# SFXboard.net
KiCad netlist of a schematic drawn in EAGLE
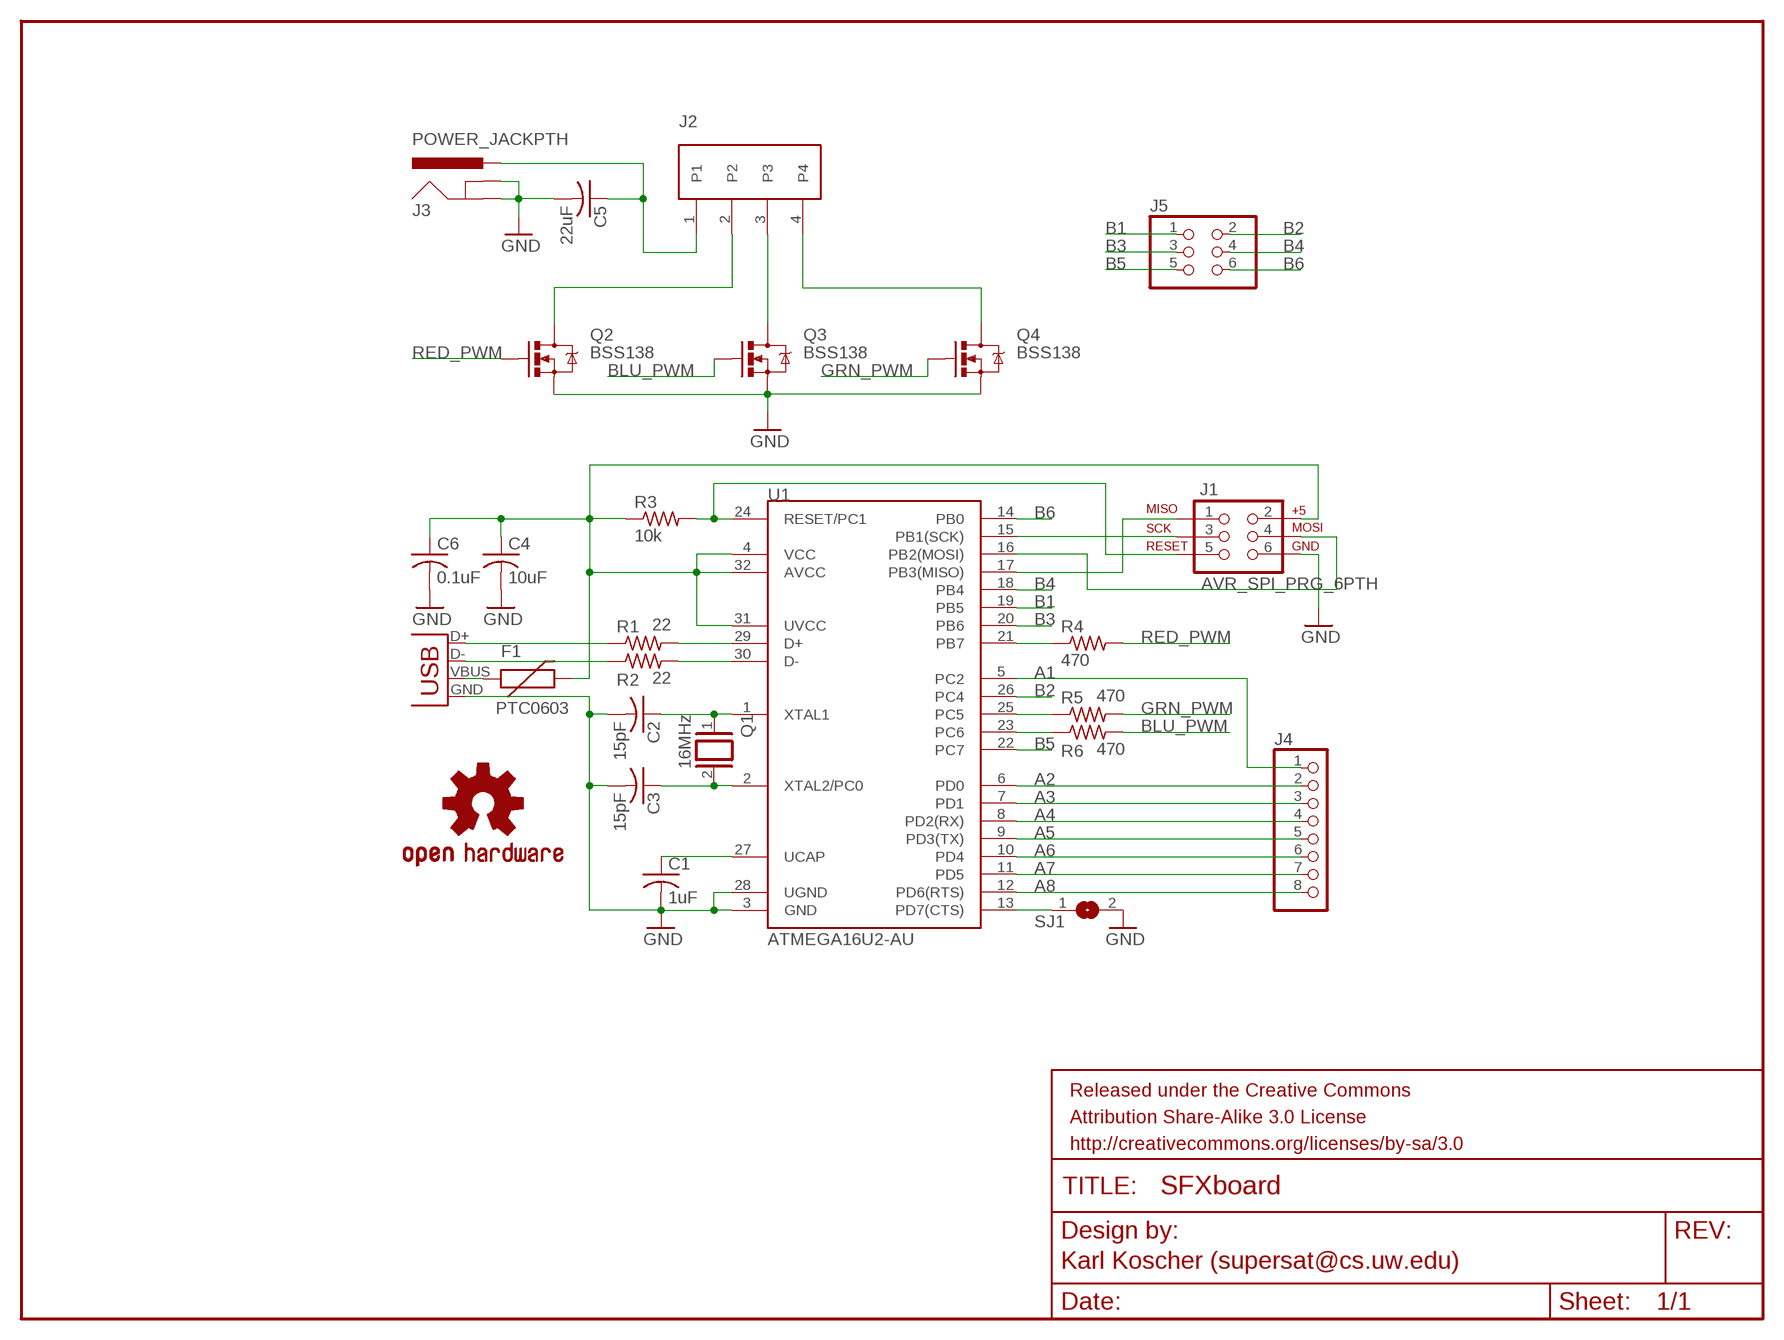
[diagram p0: schematic, sheet 1]

(export (version "E")
  (design (tool "Eeschema 10.0.6"))
  (components
    (comp (ref "C1")
      (value "1uF")
      (footprint "eagle-import:C0603")
      (libsource (lib "eagle-import") (part "C-USC0603"))
    )
    (comp (ref "C2")
      (value "15pF")
      (footprint "eagle-import:C0603")
      (libsource (lib "eagle-import") (part "C-USC0603"))
    )
    (comp (ref "C3")
      (value "15pF")
      (footprint "eagle-import:C0603")
      (libsource (lib "eagle-import") (part "C-USC0603"))
    )
    (comp (ref "C4")
      (value "10uF")
      (footprint "eagle-import:C0805")
      (libsource (lib "eagle-import") (part "C-USC0805"))
    )
    (comp (ref "C5")
      (value "22uF")
      (footprint "eagle-import:C0805")
      (libsource (lib "eagle-import") (part "C-USC0805"))
    )
    (comp (ref "C6")
      (value "0.1uF")
      (footprint "eagle-import:C0402")
      (libsource (lib "eagle-import") (part "C-USC0402"))
    )
    (comp (ref "F1")
      (value "PTC0603")
      (footprint "eagle-import:0603")
      (libsource (lib "eagle-import") (part "PTC0603"))
    )
    (comp (ref "FRAME1")
      (value "FRAME-LETTER")
      (footprint "eagle-import:CREATIVE_COMMONS")
      (libsource (lib "eagle-import") (part "FRAME-LETTER"))
    )
    (comp (ref "J1")
      (value "AVR_SPI_PRG_6PTH")
      (footprint "eagle-import:2X3")
      (libsource (lib "eagle-import") (part "AVR_SPI_PRG_6PTH"))
    )
    (comp (ref "J2")
      (value "TERMBLOCK4POS")
      (footprint "eagle-import:TERMBLOCK4P")
      (libsource (lib "eagle-import") (part "TERMBLOCK4POS"))
    )
    (comp (ref "J3")
      (value "POWER_JACKPTH")
      (footprint "eagle-import:POWER_JACK_PTH")
      (libsource (lib "eagle-import") (part "POWER_JACKPTH"))
    )
    (comp (ref "J4")
      (value "PINHD-1X8")
      (footprint "eagle-import:1X08")
      (libsource (lib "eagle-import") (part "PINHD-1X8"))
    )
    (comp (ref "J5")
      (value "PINHD-2X3")
      (footprint "eagle-import:2X03")
      (libsource (lib "eagle-import") (part "PINHD-2X3"))
    )
    (comp (ref "Q1")
      (value "16MHz")
      (footprint "eagle-import:QS")
      (libsource (lib "eagle-import") (part "XTAL/S"))
    )
    (comp (ref "Q2")
      (value "BSS138")
      (footprint "eagle-import:SOT23-3")
      (libsource (lib "eagle-import") (part "BSS138TRANS-00830"))
    )
    (comp (ref "Q3")
      (value "BSS138")
      (footprint "eagle-import:SOT23-3")
      (libsource (lib "eagle-import") (part "BSS138TRANS-00830"))
    )
    (comp (ref "Q4")
      (value "BSS138")
      (footprint "eagle-import:SOT23-3")
      (libsource (lib "eagle-import") (part "BSS138TRANS-00830"))
    )
    (comp (ref "R1")
      (value "22")
      (footprint "eagle-import:R0603")
      (libsource (lib "eagle-import") (part "R-US_R0603"))
    )
    (comp (ref "R2")
      (value "22")
      (footprint "eagle-import:R0603")
      (libsource (lib "eagle-import") (part "R-US_R0603"))
    )
    (comp (ref "R3")
      (value "10k")
      (footprint "eagle-import:R0603")
      (libsource (lib "eagle-import") (part "R-US_R0603"))
    )
    (comp (ref "R4")
      (value "470")
      (footprint "eagle-import:R0603")
      (libsource (lib "eagle-import") (part "R-US_R0603"))
    )
    (comp (ref "R5")
      (value "470")
      (footprint "eagle-import:R0603")
      (libsource (lib "eagle-import") (part "R-US_R0603"))
    )
    (comp (ref "R6")
      (value "470")
      (footprint "eagle-import:R0603")
      (libsource (lib "eagle-import") (part "R-US_R0603"))
    )
    (comp (ref "SJ1") (value "SJ") (footprint "eagle-import:SJ") (libsource (lib "eagle-import") (part "SJ")))
    (comp (ref "U$2")
      (value "OSHW-LOGOS")
      (footprint "eagle-import:OSHW-LOGO-S")
      (libsource (lib "eagle-import") (part "OSHW-LOGOS"))
    )
    (comp (ref "U1")
      (value "ATMEGA16U2-AU")
      (footprint "eagle-import:TQFP32-08")
      (libsource (lib "eagle-import") (part "ATMEGA8U2AU"))
    )
    (comp (ref "X1")
      (value "USBSMD")
      (footprint "eagle-import:USB-MINIB")
      (libsource (lib "eagle-import") (part "USBSMD"))
    )
  )
  (nets
    (net (code "1") (name "/A1") (class "Default")
      (node (ref "J4") (pin "1") (pinfunction "1_1") (pintype "passive"))
      (node (ref "U1") (pin "5") (pinfunction "PC2_5") (pintype "bidirectional"))
    )
    (net (code "2") (name "/A2") (class "Default")
      (node (ref "J4") (pin "2") (pinfunction "2_2") (pintype "passive"))
      (node (ref "U1") (pin "6") (pinfunction "PD0_6") (pintype "bidirectional"))
    )
    (net (code "3") (name "/A3") (class "Default")
      (node (ref "J4") (pin "3") (pinfunction "3_3") (pintype "passive"))
      (node (ref "U1") (pin "7") (pinfunction "PD1_7") (pintype "bidirectional"))
    )
    (net (code "4") (name "/A4") (class "Default")
      (node (ref "J4") (pin "4") (pinfunction "4_4") (pintype "passive"))
      (node (ref "U1") (pin "8") (pinfunction "PD2(RX)_8") (pintype "bidirectional"))
    )
    (net (code "5") (name "/A5") (class "Default")
      (node (ref "J4") (pin "5") (pinfunction "5_5") (pintype "passive"))
      (node (ref "U1") (pin "9") (pinfunction "PD3(TX)_9") (pintype "bidirectional"))
    )
    (net (code "6") (name "/A6") (class "Default")
      (node (ref "J4") (pin "6") (pinfunction "6_6") (pintype "passive"))
      (node (ref "U1") (pin "10") (pinfunction "PD4_10") (pintype "bidirectional"))
    )
    (net (code "7") (name "/A7") (class "Default")
      (node (ref "J4") (pin "7") (pinfunction "7_7") (pintype "passive"))
      (node (ref "U1") (pin "11") (pinfunction "PD5_11") (pintype "bidirectional"))
    )
    (net (code "8") (name "/A8") (class "Default")
      (node (ref "J4") (pin "8") (pinfunction "8_8") (pintype "passive"))
      (node (ref "U1") (pin "12") (pinfunction "PD6(RTS)_12") (pintype "bidirectional"))
    )
    (net (code "9") (name "/B1") (class "Default")
      (node (ref "J5") (pin "1") (pinfunction "1_1") (pintype "passive"))
      (node (ref "U1") (pin "19") (pinfunction "PB5_19") (pintype "bidirectional"))
    )
    (net (code "10") (name "/B2") (class "Default")
      (node (ref "J5") (pin "2") (pinfunction "2_2") (pintype "passive"))
      (node (ref "U1") (pin "26") (pinfunction "PC4_26") (pintype "bidirectional"))
    )
    (net (code "11") (name "/B3") (class "Default")
      (node (ref "J5") (pin "3") (pinfunction "3_3") (pintype "passive"))
      (node (ref "U1") (pin "20") (pinfunction "PB6_20") (pintype "bidirectional"))
    )
    (net (code "12") (name "/B4") (class "Default")
      (node (ref "J5") (pin "4") (pinfunction "4_4") (pintype "passive"))
      (node (ref "U1") (pin "18") (pinfunction "PB4_18") (pintype "bidirectional"))
    )
    (net (code "13") (name "/B5") (class "Default")
      (node (ref "J5") (pin "5") (pinfunction "5_5") (pintype "passive"))
      (node (ref "U1") (pin "22") (pinfunction "PC7_22") (pintype "bidirectional"))
    )
    (net (code "14") (name "/B6") (class "Default")
      (node (ref "J5") (pin "6") (pinfunction "6_6") (pintype "passive"))
      (node (ref "U1") (pin "14") (pinfunction "PB0_14") (pintype "bidirectional"))
    )
    (net (code "15") (name "/BLU_PWM") (class "Default")
      (node (ref "Q3") (pin "1") (pinfunction "G_1") (pintype "passive"))
      (node (ref "R6") (pin "2") (pinfunction "2_2") (pintype "passive"))
    )
    (net (code "16") (name "/GRN_PWM") (class "Default")
      (node (ref "Q4") (pin "1") (pinfunction "G_1") (pintype "passive"))
      (node (ref "R5") (pin "2") (pinfunction "2_2") (pintype "passive"))
    )
    (net (code "17") (name "/RED_PWM") (class "Default")
      (node (ref "Q2") (pin "1") (pinfunction "G_1") (pintype "passive"))
      (node (ref "R4") (pin "2") (pinfunction "2_2") (pintype "passive"))
    )
    (net (code "18") (name "GND") (class "Default")
      (node (ref "C1") (pin "2") (pinfunction "2_2") (pintype "passive"))
      (node (ref "C2") (pin "2") (pinfunction "2_2") (pintype "passive"))
      (node (ref "C3") (pin "2") (pinfunction "2_2") (pintype "passive"))
      (node (ref "C4") (pin "2") (pinfunction "2_2") (pintype "passive"))
      (node (ref "C5") (pin "2") (pinfunction "2_2") (pintype "passive"))
      (node (ref "C6") (pin "2") (pinfunction "2_2") (pintype "passive"))
      (node (ref "J1") (pin "6") (pinfunction "6_6") (pintype "passive"))
      (node (ref "J3") (pin "GND") (pinfunction "GND_GND") (pintype "bidirectional"))
      (node (ref "J3") (pin "GNDBREAK") (pinfunction "GNDBREAK_GNDBREAK") (pintype "bidirectional"))
      (node (ref "Q2") (pin "2") (pinfunction "S_2") (pintype "passive"))
      (node (ref "Q3") (pin "2") (pinfunction "S_2") (pintype "passive"))
      (node (ref "Q4") (pin "2") (pinfunction "S_2") (pintype "passive"))
      (node (ref "SJ1") (pin "2") (pinfunction "2_2") (pintype "passive"))
      (node (ref "U1") (pin "28") (pinfunction "UGND_28") (pintype "bidirectional"))
      (node (ref "U1") (pin "3") (pinfunction "GND_3") (pintype "bidirectional"))
      (node (ref "X1") (pin "GND") (pinfunction "GND_GND") (pintype "bidirectional"))
    )
    (net (code "19") (name "Net-(F1-Pad1)") (class "Default")
      (node (ref "F1") (pin "1") (pinfunction "1_1") (pintype "bidirectional"))
      (node (ref "X1") (pin "VBUS") (pinfunction "VBUS_VBUS") (pintype "bidirectional"))
    )
    (net (code "20") (name "Net-(J2-P1)") (class "Default")
      (node (ref "C5") (pin "1") (pinfunction "1_1") (pintype "passive"))
      (node (ref "J2") (pin "1") (pinfunction "P1_1") (pintype "bidirectional"))
      (node (ref "J3") (pin "PWR") (pinfunction "PWR_PWR") (pintype "bidirectional"))
    )
    (net (code "21") (name "Net-(J2-P2)") (class "Default")
      (node (ref "J2") (pin "2") (pinfunction "P2_2") (pintype "bidirectional"))
      (node (ref "Q2") (pin "3") (pinfunction "D_3") (pintype "passive"))
    )
    (net (code "22") (name "Net-(J2-P3)") (class "Default")
      (node (ref "J2") (pin "3") (pinfunction "P3_3") (pintype "bidirectional"))
      (node (ref "Q3") (pin "3") (pinfunction "D_3") (pintype "passive"))
    )
    (net (code "23") (name "Net-(J2-P4)") (class "Default")
      (node (ref "J2") (pin "4") (pinfunction "P4_4") (pintype "bidirectional"))
      (node (ref "Q4") (pin "3") (pinfunction "D_3") (pintype "passive"))
    )
    (net (code "24") (name "Net-(R1-Pad1)") (class "Default")
      (node (ref "R1") (pin "1") (pinfunction "1_1") (pintype "passive"))
      (node (ref "X1") (pin "D+") (pinfunction "D+_D+") (pintype "bidirectional"))
    )
    (net (code "25") (name "Net-(R2-Pad1)") (class "Default")
      (node (ref "R2") (pin "1") (pinfunction "1_1") (pintype "passive"))
      (node (ref "X1") (pin "D-") (pinfunction "D-_D-") (pintype "bidirectional"))
    )
    (net (code "26") (name "Net-(U1-AVCC)") (class "Default")
      (node (ref "C4") (pin "1") (pinfunction "1_1") (pintype "passive"))
      (node (ref "C6") (pin "1") (pinfunction "1_1") (pintype "passive"))
      (node (ref "F1") (pin "2") (pinfunction "2_2") (pintype "bidirectional"))
      (node (ref "J1") (pin "2") (pinfunction "2_2") (pintype "passive"))
      (node (ref "R3") (pin "1") (pinfunction "1_1") (pintype "passive"))
      (node (ref "U1") (pin "31") (pinfunction "UVCC_31") (pintype "bidirectional"))
      (node (ref "U1") (pin "32") (pinfunction "AVCC_32") (pintype "bidirectional"))
      (node (ref "U1") (pin "4") (pinfunction "VCC_4") (pintype "bidirectional"))
    )
    (net (code "27") (name "Net-(U1-D+)") (class "Default")
      (node (ref "R1") (pin "2") (pinfunction "2_2") (pintype "passive"))
      (node (ref "U1") (pin "29") (pinfunction "D+_29") (pintype "bidirectional"))
    )
    (net (code "28") (name "Net-(U1-D-)") (class "Default")
      (node (ref "R2") (pin "2") (pinfunction "2_2") (pintype "passive"))
      (node (ref "U1") (pin "30") (pinfunction "D-_30") (pintype "bidirectional"))
    )
    (net (code "29") (name "Net-(U1-PB1(SCK))") (class "Default")
      (node (ref "J1") (pin "3") (pinfunction "3_3") (pintype "passive"))
      (node (ref "U1") (pin "15") (pinfunction "PB1(SCK)_15") (pintype "bidirectional"))
    )
    (net (code "30") (name "Net-(U1-PB2(MOSI))") (class "Default")
      (node (ref "J1") (pin "4") (pinfunction "4_4") (pintype "passive"))
      (node (ref "U1") (pin "16") (pinfunction "PB2(MOSI)_16") (pintype "bidirectional"))
    )
    (net (code "31") (name "Net-(U1-PB3(MISO))") (class "Default")
      (node (ref "J1") (pin "1") (pinfunction "1_1") (pintype "passive"))
      (node (ref "U1") (pin "17") (pinfunction "PB3(MISO)_17") (pintype "bidirectional"))
    )
    (net (code "32") (name "Net-(U1-PB7)") (class "Default")
      (node (ref "R4") (pin "1") (pinfunction "1_1") (pintype "passive"))
      (node (ref "U1") (pin "21") (pinfunction "PB7_21") (pintype "bidirectional"))
    )
    (net (code "33") (name "Net-(U1-PC5)") (class "Default")
      (node (ref "R5") (pin "1") (pinfunction "1_1") (pintype "passive"))
      (node (ref "U1") (pin "25") (pinfunction "PC5_25") (pintype "bidirectional"))
    )
    (net (code "34") (name "Net-(U1-PC6)") (class "Default")
      (node (ref "R6") (pin "1") (pinfunction "1_1") (pintype "passive"))
      (node (ref "U1") (pin "23") (pinfunction "PC6_23") (pintype "bidirectional"))
    )
    (net (code "35") (name "Net-(U1-PD7(CTS))") (class "Default")
      (node (ref "SJ1") (pin "1") (pinfunction "1_1") (pintype "passive"))
      (node (ref "U1") (pin "13") (pinfunction "PD7(CTS)_13") (pintype "bidirectional"))
    )
    (net (code "36") (name "Net-(U1-RESET{slash}PC1)") (class "Default")
      (node (ref "J1") (pin "5") (pinfunction "5_5") (pintype "passive"))
      (node (ref "R3") (pin "2") (pinfunction "2_2") (pintype "passive"))
      (node (ref "U1") (pin "24") (pinfunction "RESET/PC1_24") (pintype "bidirectional"))
    )
    (net (code "37") (name "Net-(U1-UCAP)") (class "Default")
      (node (ref "C1") (pin "1") (pinfunction "1_1") (pintype "passive"))
      (node (ref "U1") (pin "27") (pinfunction "UCAP_27") (pintype "bidirectional"))
    )
    (net (code "38") (name "Net-(U1-XTAL1)") (class "Default")
      (node (ref "C2") (pin "1") (pinfunction "1_1") (pintype "passive"))
      (node (ref "Q1") (pin "1") (pinfunction "1_1") (pintype "passive"))
      (node (ref "U1") (pin "1") (pinfunction "XTAL1_1") (pintype "bidirectional"))
    )
    (net (code "39") (name "Net-(U1-XTAL2{slash}PC0)") (class "Default")
      (node (ref "C3") (pin "1") (pinfunction "1_1") (pintype "passive"))
      (node (ref "Q1") (pin "2") (pinfunction "2_2") (pintype "passive"))
      (node (ref "U1") (pin "2") (pinfunction "XTAL2/PC0_2") (pintype "bidirectional"))
    )
  )
)
